# tamiya_camrobo_face_xiao.net
KiCad netlist of a schematic drawn in EAGLE
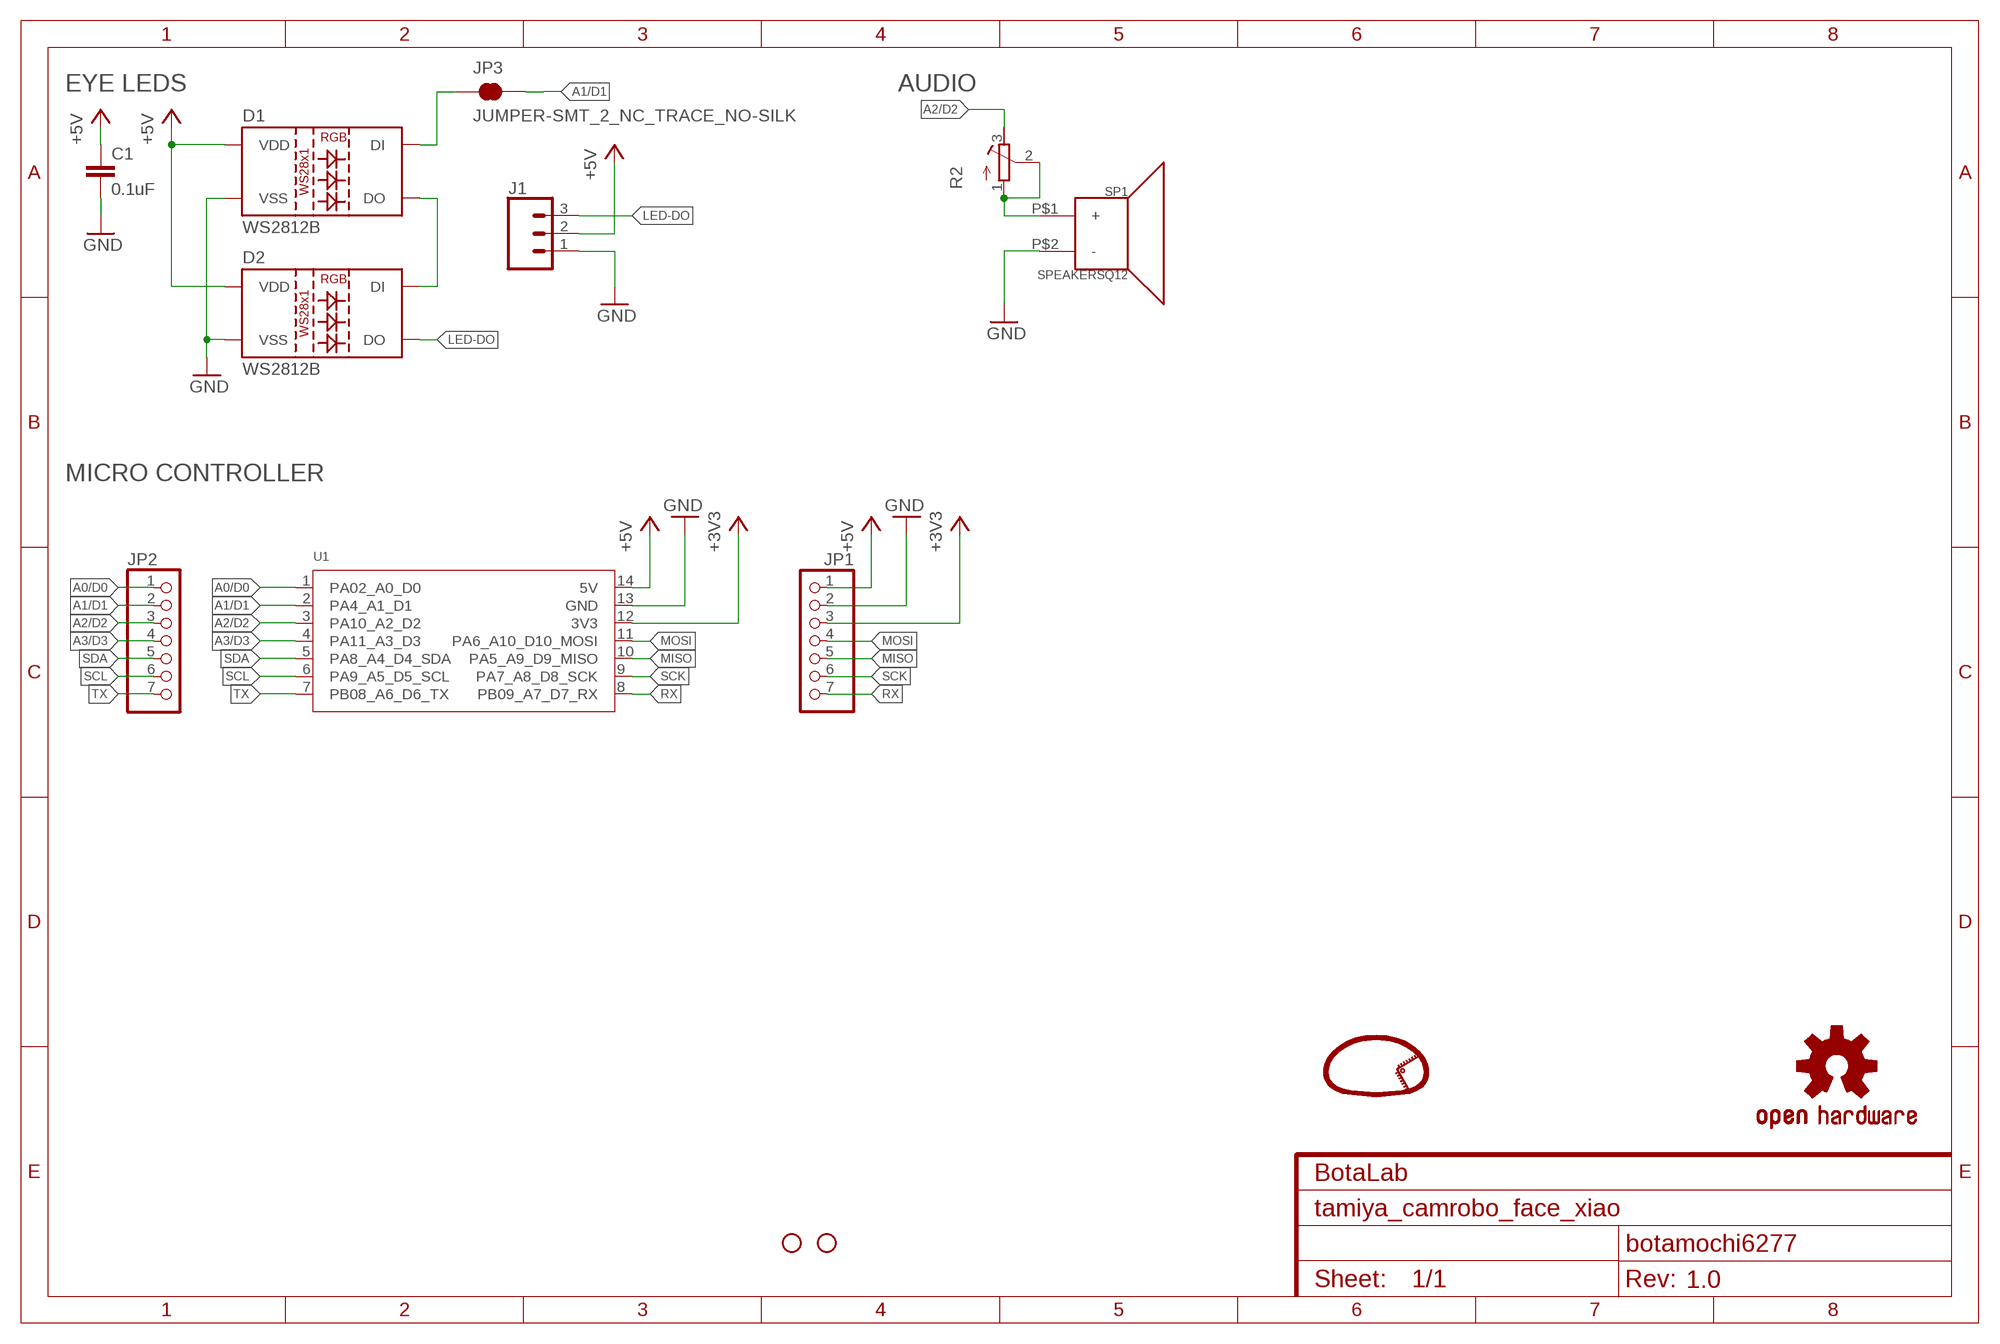
[diagram p0: schematic, sheet 1]

(export (version "E")
  (design (tool "Eeschema 10.0.6"))
  (components
    (comp (ref "C1")
      (value "0.1uF")
      (footprint "eagle-import:C1608")
      (libsource (lib "eagle-import") (part "C-EUC1608"))
    )
    (comp (ref "D1")
      (value "WS2812B")
      (footprint "eagle-import:WS2812B")
      (libsource (lib "eagle-import") (part "WS2812B"))
    )
    (comp (ref "D2")
      (value "WS2812B")
      (footprint "eagle-import:WS2812B")
      (libsource (lib "eagle-import") (part "WS2812B"))
    )
    (comp (ref "H1")
      (value "STAND-OFF")
      (footprint "eagle-import:STAND-OFF")
      (libsource (lib "eagle-import") (part "STAND-OFF"))
    )
    (comp (ref "H2")
      (value "STAND-OFF")
      (footprint "eagle-import:STAND-OFF")
      (libsource (lib "eagle-import") (part "STAND-OFF"))
    )
    (comp (ref "J1")
      (value "CONN_03")
      (footprint "eagle-import:1X03")
      (libsource (lib "eagle-import") (part "CONN_03"))
    )
    (comp (ref "JP1")
      (value "PINHD-1X7")
      (footprint "eagle-import:1X07")
      (libsource (lib "eagle-import") (part "PINHD-1X7"))
    )
    (comp (ref "JP2")
      (value "PINHD-1X7")
      (footprint "eagle-import:1X07")
      (libsource (lib "eagle-import") (part "PINHD-1X7"))
    )
    (comp (ref "JP3")
      (value "JUMPER-SMT_2_NC_TRACE_NO-SILK")
      (footprint "eagle-import:SMT-JUMPER_2_NC_TRACE_NO-SILK")
      (libsource (lib "eagle-import") (part "JUMPER-SMT_2_NC_TRACE_NO-SILK"))
    )
    (comp (ref "LOGO1")
      (value "LOGO")
      (footprint "eagle-import:LOGO")
      (libsource (lib "eagle-import") (part "LOGO"))
    )
    (comp (ref "LOGO2")
      (value "OSHW-LOGOS")
      (footprint "eagle-import:OSHW-LOGO-S")
      (libsource (lib "eagle-import") (part "OSHW-LOGOS"))
    )
    (comp (ref "R2")
      (value "R-TRIMMCVR42A")
      (footprint "eagle-import:RTRIMCVR42A")
      (libsource (lib "eagle-import") (part "R-TRIMMCVR42A"))
    )
    (comp (ref "SP1")
      (value "SPEAKERSQ12")
      (footprint "eagle-import:PKLCS1212E")
      (libsource (lib "eagle-import") (part "SPEAKERSQ12"))
    )
    (comp (ref "U1")
      (value "MOUDLE-SEEEDUINO-XIAO-MOUNTED")
      (footprint "eagle-import:MOUDLE14P-2.54-21X17.8MM-MODIFIED")
      (libsource (lib "eagle-import") (part "MOUDLE-SEEEDUINO-XIAO-MOUNTED"))
    )
  )
  (nets
    (net (code "1") (name "+3V3") (class "Default")
      (node (ref "JP1") (pin "3") (pinfunction "3_3") (pintype "passive"))
      (node (ref "U1") (pin "12") (pinfunction "3V3_12") (pintype "bidirectional"))
    )
    (net (code "2") (name "+5V") (class "Default")
      (node (ref "C1") (pin "1") (pinfunction "1_1") (pintype "passive"))
      (node (ref "D1") (pin "1") (pinfunction "VDD_1") (pintype "bidirectional"))
      (node (ref "D2") (pin "1") (pinfunction "VDD_1") (pintype "bidirectional"))
      (node (ref "J1") (pin "2") (pinfunction "2_2") (pintype "passive"))
      (node (ref "JP1") (pin "1") (pinfunction "1_1") (pintype "passive"))
      (node (ref "U1") (pin "14") (pinfunction "5V_14") (pintype "bidirectional"))
    )
    (net (code "3") (name "A0{slash}D0") (class "Default")
      (node (ref "JP2") (pin "1") (pinfunction "1_1") (pintype "passive"))
      (node (ref "U1") (pin "1") (pinfunction "PA02_A0_D0_1") (pintype "bidirectional"))
    )
    (net (code "4") (name "A1{slash}D1") (class "Default")
      (node (ref "JP2") (pin "2") (pinfunction "2_2") (pintype "passive"))
      (node (ref "JP3") (pin "2") (pinfunction "2_2") (pintype "passive"))
      (node (ref "U1") (pin "2") (pinfunction "PA4_A1_D1_2") (pintype "bidirectional"))
    )
    (net (code "5") (name "A2{slash}D2") (class "Default")
      (node (ref "JP2") (pin "3") (pinfunction "3_3") (pintype "passive"))
      (node (ref "R2") (pin "3") (pinfunction "E_3") (pintype "passive"))
      (node (ref "U1") (pin "3") (pinfunction "PA10_A2_D2_3") (pintype "bidirectional"))
    )
    (net (code "6") (name "A3{slash}D3") (class "Default")
      (node (ref "JP2") (pin "4") (pinfunction "4_4") (pintype "passive"))
      (node (ref "U1") (pin "4") (pinfunction "PA11_A3_D3_4") (pintype "bidirectional"))
    )
    (net (code "7") (name "GND") (class "Default")
      (node (ref "C1") (pin "2") (pinfunction "2_2") (pintype "passive"))
      (node (ref "D1") (pin "3") (pinfunction "VSS_3") (pintype "bidirectional"))
      (node (ref "D2") (pin "3") (pinfunction "VSS_3") (pintype "bidirectional"))
      (node (ref "J1") (pin "1") (pinfunction "1_1") (pintype "passive"))
      (node (ref "JP1") (pin "2") (pinfunction "2_2") (pintype "passive"))
      (node (ref "SP1") (pin "P$2") (pinfunction "-_P$2") (pintype "bidirectional"))
      (node (ref "U1") (pin "13") (pinfunction "GND_13") (pintype "bidirectional"))
    )
    (net (code "8") (name "LED-DO") (class "Default")
      (node (ref "D2") (pin "2") (pinfunction "DO_2") (pintype "bidirectional"))
      (node (ref "J1") (pin "3") (pinfunction "3_3") (pintype "passive"))
    )
    (net (code "9") (name "MISO") (class "Default")
      (node (ref "JP1") (pin "5") (pinfunction "5_5") (pintype "passive"))
      (node (ref "U1") (pin "10") (pinfunction "PA5_A9_D9_MISO_10") (pintype "bidirectional"))
    )
    (net (code "10") (name "MOSI") (class "Default")
      (node (ref "JP1") (pin "4") (pinfunction "4_4") (pintype "passive"))
      (node (ref "U1") (pin "11") (pinfunction "PA6_A10_D10_MOSI_11") (pintype "bidirectional"))
    )
    (net (code "11") (name "Net-(D1-DI)") (class "Default")
      (node (ref "D1") (pin "4") (pinfunction "DI_4") (pintype "bidirectional"))
      (node (ref "JP3") (pin "1") (pinfunction "1_1") (pintype "passive"))
    )
    (net (code "12") (name "Net-(D1-DO)") (class "Default")
      (node (ref "D1") (pin "2") (pinfunction "DO_2") (pintype "bidirectional"))
      (node (ref "D2") (pin "4") (pinfunction "DI_4") (pintype "bidirectional"))
    )
    (net (code "13") (name "Net-(R2-A)") (class "Default")
      (node (ref "R2") (pin "1") (pinfunction "A_1") (pintype "passive"))
      (node (ref "R2") (pin "2") (pinfunction "S_2") (pintype "passive"))
      (node (ref "SP1") (pin "P$1") (pinfunction "+_P$1") (pintype "bidirectional"))
    )
    (net (code "14") (name "RX") (class "Default")
      (node (ref "JP1") (pin "7") (pinfunction "7_7") (pintype "passive"))
      (node (ref "U1") (pin "8") (pinfunction "PB09_A7_D7_RX_8") (pintype "bidirectional"))
    )
    (net (code "15") (name "SCK") (class "Default")
      (node (ref "JP1") (pin "6") (pinfunction "6_6") (pintype "passive"))
      (node (ref "U1") (pin "9") (pinfunction "PA7_A8_D8_SCK_9") (pintype "bidirectional"))
    )
    (net (code "16") (name "SCL") (class "Default")
      (node (ref "JP2") (pin "6") (pinfunction "6_6") (pintype "passive"))
      (node (ref "U1") (pin "6") (pinfunction "PA9_A5_D5_SCL_6") (pintype "bidirectional"))
    )
    (net (code "17") (name "SDA") (class "Default")
      (node (ref "JP2") (pin "5") (pinfunction "5_5") (pintype "passive"))
      (node (ref "U1") (pin "5") (pinfunction "PA8_A4_D4_SDA_5") (pintype "bidirectional"))
    )
    (net (code "18") (name "TX") (class "Default")
      (node (ref "JP2") (pin "7") (pinfunction "7_7") (pintype "passive"))
      (node (ref "U1") (pin "7") (pinfunction "PB08_A6_D6_TX_7") (pintype "bidirectional"))
    )
  )
)
